# neogeo2tg16_13.net
KiCad netlist of a schematic drawn in EAGLE
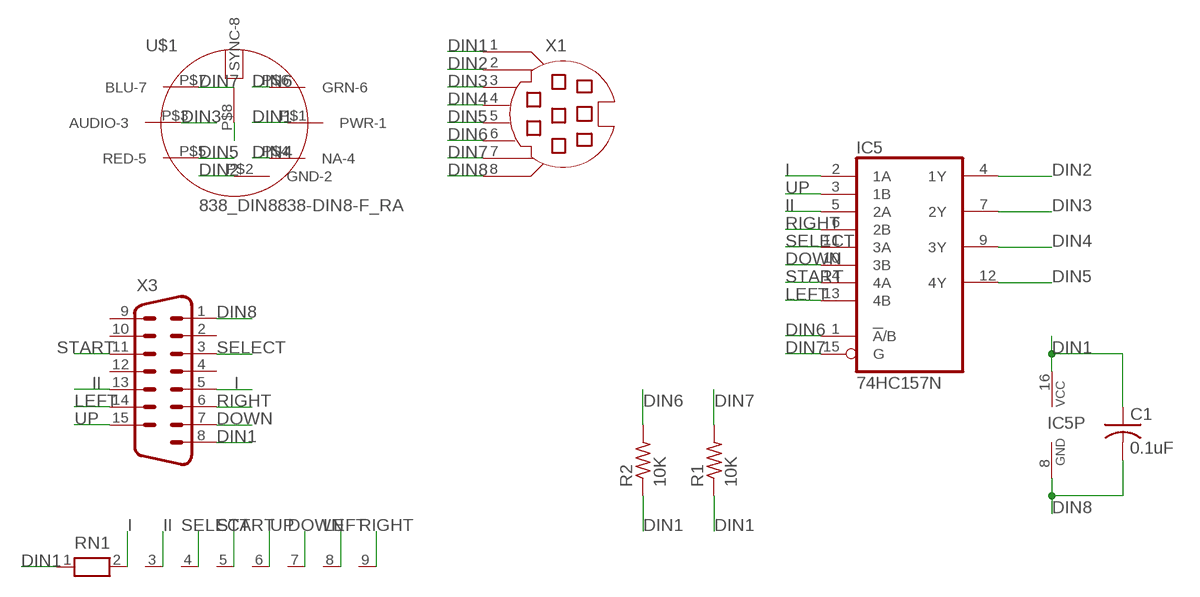
[diagram p0: schematic, sheet 1]

(export (version "E")
  (design (tool "Eeschema 10.0.6"))
  (components
    (comp (ref "C1")
      (value "0.1uF")
      (footprint "eagle-import:C025-024X044")
      (libsource (lib "eagle-import") (part "C-US025-024X044"))
    )
    (comp (ref "IC5")
      (value "74HC157N")
      (footprint "eagle-import:DIL16")
      (libsource (lib "eagle-import") (part "74157NHC"))
    )
    (comp (ref "R1")
      (value "10K")
      (footprint "eagle-import:0204_7")
      (libsource (lib "eagle-import") (part "R-US_0204/7"))
    )
    (comp (ref "R2")
      (value "10K")
      (footprint "eagle-import:0204_7")
      (libsource (lib "eagle-import") (part "R-US_0204/7"))
    )
    (comp (ref "RN1")
      (value "RN08")
      (footprint "eagle-import:RN-9")
      (libsource (lib "eagle-import") (part "RN08"))
    )
    (comp (ref "U$1")
      (value "838_DIN8838-DIN8-F_RA")
      (footprint "eagle-import:838_DIN8")
      (libsource (lib "eagle-import") (part "838_DIN8838-DIN8-F_RA"))
    )
    (comp (ref "X1")
      (value "MD08SS")
      (footprint "eagle-import:MDIN08SS")
      (libsource (lib "eagle-import") (part "MD08SS"))
    )
    (comp (ref "X3")
      (value "M15HP")
      (footprint "eagle-import:M15HP")
      (libsource (lib "eagle-import") (part "M15HP"))
    )
  )
  (nets
    (net (code "1") (name "/DIN1") (class "Default")
      (node (ref "C1") (pin "1") (pinfunction "1_1") (pintype "passive"))
      (node (ref "IC5") (pin "16") (pinfunction "VCC_16") (pintype "power_in"))
      (node (ref "R1") (pin "1") (pinfunction "1_1") (pintype "passive"))
      (node (ref "R2") (pin "1") (pinfunction "1_1") (pintype "passive"))
      (node (ref "RN1") (pin "1") (pinfunction "1_1") (pintype "passive"))
      (node (ref "U$1") (pin "P$1") (pinfunction "PWR-1_P$1") (pintype "power_in"))
      (node (ref "X1") (pin "1") (pinfunction "1_1") (pintype "passive"))
      (node (ref "X3") (pin "8") (pinfunction "8_8") (pintype "passive"))
    )
    (net (code "2") (name "/DIN2") (class "Default")
      (node (ref "IC5") (pin "4") (pinfunction "1Y_4") (pintype "output"))
      (node (ref "U$1") (pin "P$2") (pinfunction "GND-2_P$2") (pintype "bidirectional"))
      (node (ref "X1") (pin "2") (pinfunction "2_2") (pintype "passive"))
    )
    (net (code "3") (name "/DIN3") (class "Default")
      (node (ref "IC5") (pin "7") (pinfunction "2Y_7") (pintype "output"))
      (node (ref "U$1") (pin "P$3") (pinfunction "AUDIO-3_P$3") (pintype "bidirectional"))
      (node (ref "X1") (pin "3") (pinfunction "3_3") (pintype "passive"))
    )
    (net (code "4") (name "/DIN4") (class "Default")
      (node (ref "IC5") (pin "9") (pinfunction "3Y_9") (pintype "output"))
      (node (ref "U$1") (pin "P$4") (pinfunction "NA-4_P$4") (pintype "bidirectional"))
      (node (ref "X1") (pin "4") (pinfunction "4_4") (pintype "passive"))
    )
    (net (code "5") (name "/DIN5") (class "Default")
      (node (ref "IC5") (pin "12") (pinfunction "4Y_12") (pintype "output"))
      (node (ref "U$1") (pin "P$5") (pinfunction "RED-5_P$5") (pintype "bidirectional"))
      (node (ref "X1") (pin "5") (pinfunction "5_5") (pintype "passive"))
    )
    (net (code "6") (name "/DIN6") (class "Default")
      (node (ref "IC5") (pin "1") (pinfunction "~{A}/B_1") (pintype "input"))
      (node (ref "R2") (pin "2") (pinfunction "2_2") (pintype "passive"))
      (node (ref "U$1") (pin "P$6") (pinfunction "GRN-6_P$6") (pintype "bidirectional"))
      (node (ref "X1") (pin "6") (pinfunction "6_6") (pintype "passive"))
    )
    (net (code "7") (name "/DIN7") (class "Default")
      (node (ref "IC5") (pin "15") (pinfunction "G_15") (pintype "input"))
      (node (ref "R1") (pin "2") (pinfunction "2_2") (pintype "passive"))
      (node (ref "U$1") (pin "P$7") (pinfunction "BLU-7_P$7") (pintype "bidirectional"))
      (node (ref "X1") (pin "7") (pinfunction "7_7") (pintype "passive"))
    )
    (net (code "8") (name "/DIN8") (class "Default")
      (node (ref "C1") (pin "2") (pinfunction "2_2") (pintype "passive"))
      (node (ref "IC5") (pin "8") (pinfunction "GND_8") (pintype "power_in"))
      (node (ref "U$1") (pin "P$8") (pinfunction "SYNC-8_P$8") (pintype "bidirectional"))
      (node (ref "X1") (pin "8") (pinfunction "8_8") (pintype "passive"))
      (node (ref "X3") (pin "1") (pinfunction "1_1") (pintype "passive"))
    )
    (net (code "9") (name "/DOWN") (class "Default")
      (node (ref "IC5") (pin "10") (pinfunction "3B_10") (pintype "input"))
      (node (ref "RN1") (pin "7") (pinfunction "7_7") (pintype "passive"))
      (node (ref "X3") (pin "7") (pinfunction "7_7") (pintype "passive"))
    )
    (net (code "10") (name "/I") (class "Default")
      (node (ref "IC5") (pin "2") (pinfunction "1A_2") (pintype "input"))
      (node (ref "RN1") (pin "2") (pinfunction "2_2") (pintype "passive"))
      (node (ref "X3") (pin "5") (pinfunction "5_5") (pintype "passive"))
    )
    (net (code "11") (name "/II") (class "Default")
      (node (ref "IC5") (pin "5") (pinfunction "2A_5") (pintype "input"))
      (node (ref "RN1") (pin "3") (pinfunction "3_3") (pintype "passive"))
      (node (ref "X3") (pin "13") (pinfunction "13_13") (pintype "passive"))
    )
    (net (code "12") (name "/LEFT") (class "Default")
      (node (ref "IC5") (pin "13") (pinfunction "4B_13") (pintype "input"))
      (node (ref "RN1") (pin "8") (pinfunction "8_8") (pintype "passive"))
      (node (ref "X3") (pin "14") (pinfunction "14_14") (pintype "passive"))
    )
    (net (code "13") (name "/RIGHT") (class "Default")
      (node (ref "IC5") (pin "6") (pinfunction "2B_6") (pintype "input"))
      (node (ref "RN1") (pin "9") (pinfunction "9_9") (pintype "passive"))
      (node (ref "X3") (pin "6") (pinfunction "6_6") (pintype "passive"))
    )
    (net (code "14") (name "/SELECT") (class "Default")
      (node (ref "IC5") (pin "11") (pinfunction "3A_11") (pintype "input"))
      (node (ref "RN1") (pin "4") (pinfunction "4_4") (pintype "passive"))
      (node (ref "X3") (pin "3") (pinfunction "3_3") (pintype "passive"))
    )
    (net (code "15") (name "/START") (class "Default")
      (node (ref "IC5") (pin "14") (pinfunction "4A_14") (pintype "input"))
      (node (ref "RN1") (pin "5") (pinfunction "5_5") (pintype "passive"))
      (node (ref "X3") (pin "11") (pinfunction "11_11") (pintype "passive"))
    )
    (net (code "16") (name "/UP") (class "Default")
      (node (ref "IC5") (pin "3") (pinfunction "1B_3") (pintype "input"))
      (node (ref "RN1") (pin "6") (pinfunction "6_6") (pintype "passive"))
      (node (ref "X3") (pin "15") (pinfunction "15_15") (pintype "passive"))
    )
    (net (code "17") (name "unconnected-(X3-Pad2)") (class "Default")
      (node (ref "X3") (pin "2") (pinfunction "2_2") (pintype "passive"))
    )
    (net (code "18") (name "unconnected-(X3-Pad4)") (class "Default")
      (node (ref "X3") (pin "4") (pinfunction "4_4") (pintype "passive"))
    )
    (net (code "19") (name "unconnected-(X3-Pad9)") (class "Default")
      (node (ref "X3") (pin "9") (pinfunction "9_9") (pintype "passive"))
    )
    (net (code "20") (name "unconnected-(X3-Pad10)") (class "Default")
      (node (ref "X3") (pin "10") (pinfunction "10_10") (pintype "passive"))
    )
    (net (code "21") (name "unconnected-(X3-Pad12)") (class "Default")
      (node (ref "X3") (pin "12") (pinfunction "12_12") (pintype "passive"))
    )
  )
)
